# design.net
KiCad netlist of a schematic drawn in Altium Designer
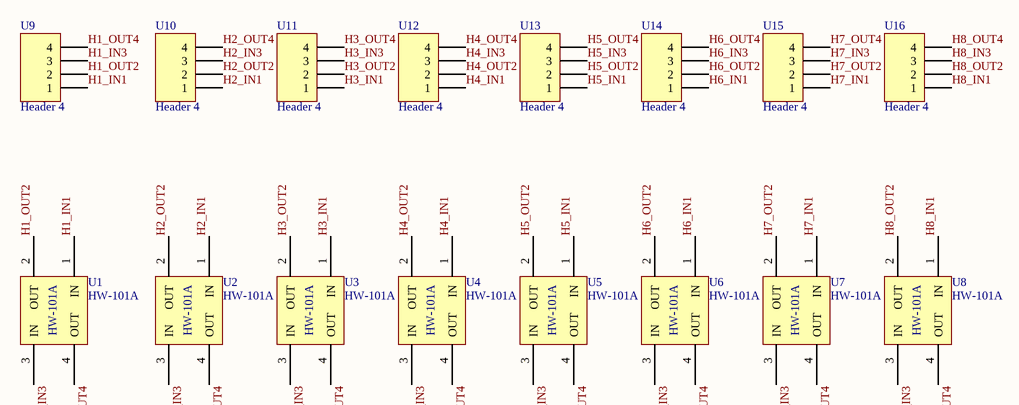
[diagram p0: 检测板.SchDoc]

(export (version "E")
  (design (tool "Eeschema 10.0.6"))
  (components
    (comp (ref "U1") (value "HW-101A") (footprint "SOT-23-4") (libsource (lib "磁导航") (part "HW-101A")))
    (comp (ref "U2") (value "HW-101A") (footprint "SOT-23-4") (libsource (lib "磁导航") (part "HW-101A")))
    (comp (ref "U3") (value "HW-101A") (footprint "SOT-23-4") (libsource (lib "磁导航") (part "HW-101A")))
    (comp (ref "U4") (value "HW-101A") (footprint "SOT-23-4") (libsource (lib "磁导航") (part "HW-101A")))
    (comp (ref "U5") (value "HW-101A") (footprint "SOT-23-4") (libsource (lib "磁导航") (part "HW-101A")))
    (comp (ref "U6") (value "HW-101A") (footprint "SOT-23-4") (libsource (lib "磁导航") (part "HW-101A")))
    (comp (ref "U7") (value "HW-101A") (footprint "SOT-23-4") (libsource (lib "磁导航") (part "HW-101A")))
    (comp (ref "U8") (value "HW-101A") (footprint "SOT-23-4") (libsource (lib "磁导航") (part "HW-101A")))
    (comp (ref "U9")
      (value "Header 4")
      (footprint "PIN4")
      (description "Header, 4-Pin")
      (fields (field (name "PUBLISHER") "Altium Limited"))
      (libsource (lib "Miscellaneous Connectors") (part "Header 4"))
    )
    (comp (ref "U10")
      (value "Header 4")
      (footprint "PIN4")
      (description "Header, 4-Pin")
      (fields (field (name "PUBLISHER") "Altium Limited"))
      (libsource (lib "Miscellaneous Connectors") (part "Header 4"))
    )
    (comp (ref "U11")
      (value "Header 4")
      (footprint "PIN4")
      (description "Header, 4-Pin")
      (fields (field (name "PUBLISHER") "Altium Limited"))
      (libsource (lib "Miscellaneous Connectors") (part "Header 4"))
    )
    (comp (ref "U12")
      (value "Header 4")
      (footprint "PIN4")
      (description "Header, 4-Pin")
      (fields (field (name "PUBLISHER") "Altium Limited"))
      (libsource (lib "Miscellaneous Connectors") (part "Header 4"))
    )
    (comp (ref "U13")
      (value "Header 4")
      (footprint "PIN4")
      (description "Header, 4-Pin")
      (fields (field (name "PUBLISHER") "Altium Limited"))
      (libsource (lib "Miscellaneous Connectors") (part "Header 4"))
    )
    (comp (ref "U14")
      (value "Header 4")
      (footprint "PIN4")
      (description "Header, 4-Pin")
      (fields (field (name "PUBLISHER") "Altium Limited"))
      (libsource (lib "Miscellaneous Connectors") (part "Header 4"))
    )
    (comp (ref "U15")
      (value "Header 4")
      (footprint "PIN4")
      (description "Header, 4-Pin")
      (fields (field (name "PUBLISHER") "Altium Limited"))
      (libsource (lib "Miscellaneous Connectors") (part "Header 4"))
    )
    (comp (ref "U16")
      (value "Header 4")
      (footprint "PIN4")
      (description "Header, 4-Pin")
      (fields (field (name "PUBLISHER") "Altium Limited"))
      (libsource (lib "Miscellaneous Connectors") (part "Header 4"))
    )
  )
  (nets
    (net (code "1") (name "/H1_IN1") (class "Default")
      (node (ref "U1") (pin "1") (pinfunction "IN_1") (pintype "passive"))
      (node (ref "U9") (pin "1") (pinfunction "1_1") (pintype "passive"))
    )
    (net (code "2") (name "/H1_IN3") (class "Default")
      (node (ref "U1") (pin "3") (pinfunction "IN_3") (pintype "passive"))
      (node (ref "U9") (pin "3") (pinfunction "3_3") (pintype "passive"))
    )
    (net (code "3") (name "/H1_OUT2") (class "Default")
      (node (ref "U1") (pin "2") (pinfunction "OUT_2") (pintype "passive"))
      (node (ref "U9") (pin "2") (pinfunction "2_2") (pintype "passive"))
    )
    (net (code "4") (name "/H1_OUT4") (class "Default")
      (node (ref "U1") (pin "4") (pinfunction "OUT_4") (pintype "passive"))
      (node (ref "U9") (pin "4") (pinfunction "4_4") (pintype "passive"))
    )
    (net (code "5") (name "/H2_IN1") (class "Default")
      (node (ref "U10") (pin "1") (pinfunction "1_1") (pintype "passive"))
      (node (ref "U2") (pin "1") (pinfunction "IN_1") (pintype "passive"))
    )
    (net (code "6") (name "/H2_IN3") (class "Default")
      (node (ref "U10") (pin "3") (pinfunction "3_3") (pintype "passive"))
      (node (ref "U2") (pin "3") (pinfunction "IN_3") (pintype "passive"))
    )
    (net (code "7") (name "/H2_OUT2") (class "Default")
      (node (ref "U10") (pin "2") (pinfunction "2_2") (pintype "passive"))
      (node (ref "U2") (pin "2") (pinfunction "OUT_2") (pintype "passive"))
    )
    (net (code "8") (name "/H2_OUT4") (class "Default")
      (node (ref "U10") (pin "4") (pinfunction "4_4") (pintype "passive"))
      (node (ref "U2") (pin "4") (pinfunction "OUT_4") (pintype "passive"))
    )
    (net (code "9") (name "/H3_IN1") (class "Default")
      (node (ref "U11") (pin "1") (pinfunction "1_1") (pintype "passive"))
      (node (ref "U3") (pin "1") (pinfunction "IN_1") (pintype "passive"))
    )
    (net (code "10") (name "/H3_IN3") (class "Default")
      (node (ref "U11") (pin "3") (pinfunction "3_3") (pintype "passive"))
      (node (ref "U3") (pin "3") (pinfunction "IN_3") (pintype "passive"))
    )
    (net (code "11") (name "/H3_OUT2") (class "Default")
      (node (ref "U11") (pin "2") (pinfunction "2_2") (pintype "passive"))
      (node (ref "U3") (pin "2") (pinfunction "OUT_2") (pintype "passive"))
    )
    (net (code "12") (name "/H3_OUT4") (class "Default")
      (node (ref "U11") (pin "4") (pinfunction "4_4") (pintype "passive"))
      (node (ref "U3") (pin "4") (pinfunction "OUT_4") (pintype "passive"))
    )
    (net (code "13") (name "/H4_IN1") (class "Default")
      (node (ref "U12") (pin "1") (pinfunction "1_1") (pintype "passive"))
      (node (ref "U4") (pin "1") (pinfunction "IN_1") (pintype "passive"))
    )
    (net (code "14") (name "/H4_IN3") (class "Default")
      (node (ref "U12") (pin "3") (pinfunction "3_3") (pintype "passive"))
      (node (ref "U4") (pin "3") (pinfunction "IN_3") (pintype "passive"))
    )
    (net (code "15") (name "/H4_OUT2") (class "Default")
      (node (ref "U12") (pin "2") (pinfunction "2_2") (pintype "passive"))
      (node (ref "U4") (pin "2") (pinfunction "OUT_2") (pintype "passive"))
    )
    (net (code "16") (name "/H4_OUT4") (class "Default")
      (node (ref "U12") (pin "4") (pinfunction "4_4") (pintype "passive"))
      (node (ref "U4") (pin "4") (pinfunction "OUT_4") (pintype "passive"))
    )
    (net (code "17") (name "/H5_IN1") (class "Default")
      (node (ref "U13") (pin "1") (pinfunction "1_1") (pintype "passive"))
      (node (ref "U5") (pin "1") (pinfunction "IN_1") (pintype "passive"))
    )
    (net (code "18") (name "/H5_IN3") (class "Default")
      (node (ref "U13") (pin "3") (pinfunction "3_3") (pintype "passive"))
      (node (ref "U5") (pin "3") (pinfunction "IN_3") (pintype "passive"))
    )
    (net (code "19") (name "/H5_OUT2") (class "Default")
      (node (ref "U13") (pin "2") (pinfunction "2_2") (pintype "passive"))
      (node (ref "U5") (pin "2") (pinfunction "OUT_2") (pintype "passive"))
    )
    (net (code "20") (name "/H5_OUT4") (class "Default")
      (node (ref "U13") (pin "4") (pinfunction "4_4") (pintype "passive"))
      (node (ref "U5") (pin "4") (pinfunction "OUT_4") (pintype "passive"))
    )
    (net (code "21") (name "/H6_IN1") (class "Default")
      (node (ref "U14") (pin "1") (pinfunction "1_1") (pintype "passive"))
      (node (ref "U6") (pin "1") (pinfunction "IN_1") (pintype "passive"))
    )
    (net (code "22") (name "/H6_IN3") (class "Default")
      (node (ref "U14") (pin "3") (pinfunction "3_3") (pintype "passive"))
      (node (ref "U6") (pin "3") (pinfunction "IN_3") (pintype "passive"))
    )
    (net (code "23") (name "/H6_OUT2") (class "Default")
      (node (ref "U14") (pin "2") (pinfunction "2_2") (pintype "passive"))
      (node (ref "U6") (pin "2") (pinfunction "OUT_2") (pintype "passive"))
    )
    (net (code "24") (name "/H6_OUT4") (class "Default")
      (node (ref "U14") (pin "4") (pinfunction "4_4") (pintype "passive"))
      (node (ref "U6") (pin "4") (pinfunction "OUT_4") (pintype "passive"))
    )
    (net (code "25") (name "/H7_IN1") (class "Default")
      (node (ref "U15") (pin "1") (pinfunction "1_1") (pintype "passive"))
      (node (ref "U7") (pin "1") (pinfunction "IN_1") (pintype "passive"))
    )
    (net (code "26") (name "/H7_IN3") (class "Default")
      (node (ref "U15") (pin "3") (pinfunction "3_3") (pintype "passive"))
      (node (ref "U7") (pin "3") (pinfunction "IN_3") (pintype "passive"))
    )
    (net (code "27") (name "/H7_OUT2") (class "Default")
      (node (ref "U15") (pin "2") (pinfunction "2_2") (pintype "passive"))
      (node (ref "U7") (pin "2") (pinfunction "OUT_2") (pintype "passive"))
    )
    (net (code "28") (name "/H7_OUT4") (class "Default")
      (node (ref "U15") (pin "4") (pinfunction "4_4") (pintype "passive"))
      (node (ref "U7") (pin "4") (pinfunction "OUT_4") (pintype "passive"))
    )
    (net (code "29") (name "/H8_IN1") (class "Default")
      (node (ref "U16") (pin "1") (pinfunction "1_1") (pintype "passive"))
      (node (ref "U8") (pin "1") (pinfunction "IN_1") (pintype "passive"))
    )
    (net (code "30") (name "/H8_IN3") (class "Default")
      (node (ref "U16") (pin "3") (pinfunction "3_3") (pintype "passive"))
      (node (ref "U8") (pin "3") (pinfunction "IN_3") (pintype "passive"))
    )
    (net (code "31") (name "/H8_OUT2") (class "Default")
      (node (ref "U16") (pin "2") (pinfunction "2_2") (pintype "passive"))
      (node (ref "U8") (pin "2") (pinfunction "OUT_2") (pintype "passive"))
    )
    (net (code "32") (name "/H8_OUT4") (class "Default")
      (node (ref "U16") (pin "4") (pinfunction "4_4") (pintype "passive"))
      (node (ref "U8") (pin "4") (pinfunction "OUT_4") (pintype "passive"))
    )
  )
)
